# PCBPayloadV6.net
KiCad netlist of a schematic drawn in EAGLE
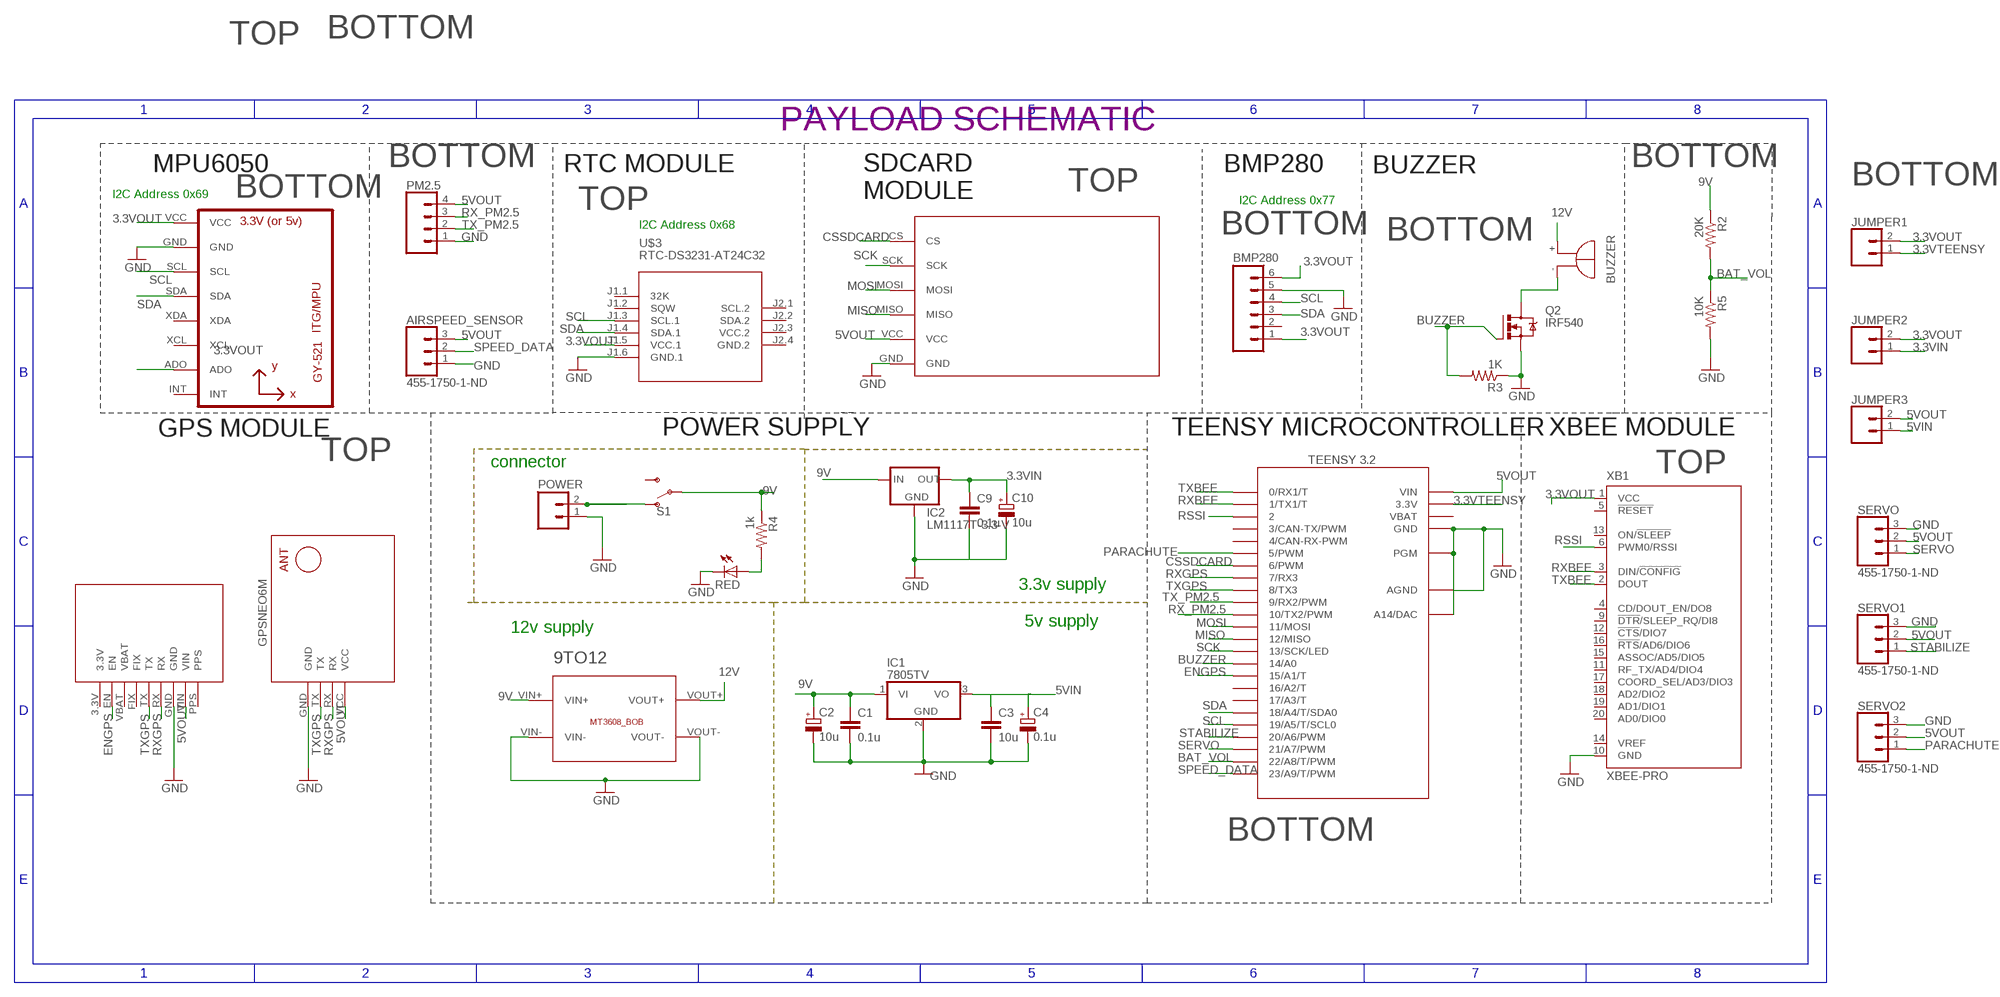
[diagram p0: schematic, sheet 1]

(export (version "E")
  (design (tool "Eeschema 10.0.6"))
  (components
    (comp (ref "9TO12")
      (value "BREAKOUTS_MT3608_BOB")
      (footprint "eagle-import:BREAKOUTS_MT3608_BOB")
      (libsource (lib "eagle-import") (part "BREAKOUTS_MT3608_BOB"))
    )
    (comp (ref "AIRSPEED_SENSOR")
      (value "455-1750-1-ND")
      (footprint "eagle-import:1X03")
      (libsource (lib "eagle-import") (part "CONN_03"))
    )
    (comp (ref "BMP280")
      (value "M06")
      (footprint "eagle-import:06P")
      (libsource (lib "eagle-import") (part "M06"))
    )
    (comp (ref "C1")
      (value "0.1u")
      (footprint "eagle-import:C025-025X050")
      (libsource (lib "eagle-import") (part "C-EU025-025X050"))
    )
    (comp (ref "C2")
      (value "10u")
      (footprint "eagle-import:E2,5-6")
      (libsource (lib "eagle-import") (part "CPOL-EUE2.5-6"))
    )
    (comp (ref "C3")
      (value "10u")
      (footprint "eagle-import:C025-025X050")
      (libsource (lib "eagle-import") (part "C-EU025-025X050"))
    )
    (comp (ref "C4")
      (value "0.1u")
      (footprint "eagle-import:E2,5-6")
      (libsource (lib "eagle-import") (part "CPOL-EUE2.5-6"))
    )
    (comp (ref "C9")
      (value "0.1u")
      (footprint "eagle-import:C025-025X050")
      (libsource (lib "eagle-import") (part "C-EU025-025X050"))
    )
    (comp (ref "C10")
      (value "10u")
      (footprint "eagle-import:E2,5-6")
      (libsource (lib "eagle-import") (part "CPOL-EUE2.5-6"))
    )
    (comp (ref "IC1")
      (value "7805TV")
      (footprint "eagle-import:TO220V")
      (libsource (lib "eagle-import") (part "78TV05"))
    )
    (comp (ref "IC2")
      (value "LM1117T-3.3-V")
      (footprint "eagle-import:TO220V")
      (libsource (lib "eagle-import") (part "LM1117T--V3.3"))
    )
    (comp (ref "JUMPER1")
      (value "CONN_02")
      (footprint "eagle-import:1X02")
      (libsource (lib "eagle-import") (part "CONN_02"))
    )
    (comp (ref "JUMPER2")
      (value "CONN_02")
      (footprint "eagle-import:1X02")
      (libsource (lib "eagle-import") (part "CONN_02"))
    )
    (comp (ref "JUMPER3")
      (value "CONN_02")
      (footprint "eagle-import:1X02")
      (libsource (lib "eagle-import") (part "CONN_02"))
    )
    (comp (ref "PM2.5")
      (value "CONN_04")
      (footprint "eagle-import:1X04")
      (libsource (lib "eagle-import") (part "CONN_04"))
    )
    (comp (ref "POWER")
      (value "CEDT_JANUARY_2015_V5_M02")
      (footprint "eagle-import:CEDT_JANUARY_2015_V5_02P")
      (libsource (lib "eagle-import") (part "CEDT_JANUARY_2015_V5_M02"))
    )
    (comp (ref "Q2")
      (value "IRF540")
      (footprint "eagle-import:TO220BV")
      (libsource (lib "eagle-import") (part "IRF540"))
    )
    (comp (ref "R2")
      (value "20K")
      (footprint "eagle-import:0204_7")
      (libsource (lib "eagle-import") (part "R-US_0204/7"))
    )
    (comp (ref "R3")
      (value "1K")
      (footprint "eagle-import:0204_7")
      (libsource (lib "eagle-import") (part "R-US_0204/7"))
    )
    (comp (ref "R4")
      (value "1k")
      (footprint "eagle-import:0204_7")
      (libsource (lib "eagle-import") (part "R-US_0204/7"))
    )
    (comp (ref "R5")
      (value "10K")
      (footprint "eagle-import:0204_7")
      (libsource (lib "eagle-import") (part "R-US_0204/7"))
    )
    (comp (ref "RED")
      (value "red")
      (footprint "eagle-import:LED3MM")
      (libsource (lib "eagle-import") (part "LED3MM"))
    )
    (comp (ref "S1")
      (value "SWITCH-SPDT-PTH-11.6X4.0MM")
      (footprint "eagle-import:SWITCH_SPDT_PTH_11.6X4.0MM")
      (libsource (lib "eagle-import") (part "SWITCH-SPDT-PTH-11.6X4.0MM"))
    )
    (comp (ref "SERVO")
      (value "455-1750-1-ND")
      (footprint "eagle-import:1X03")
      (libsource (lib "eagle-import") (part "CONN_03"))
    )
    (comp (ref "SERVO1")
      (value "455-1750-1-ND")
      (footprint "eagle-import:1X03")
      (libsource (lib "eagle-import") (part "CONN_03"))
    )
    (comp (ref "SERVO2")
      (value "455-1750-1-ND")
      (footprint "eagle-import:1X03")
      (libsource (lib "eagle-import") (part "CONN_03"))
    )
    (comp (ref "SG1")
      (value "BUZZER_EB2209A")
      (footprint "eagle-import:BUZZER_EB2209A")
      (libsource (lib "eagle-import") (part "BUZZER_EB2209A"))
    )
    (comp (ref "U$1")
      (value "GPS-RECEIVER-NEO6M")
      (footprint "eagle-import:GPS-RECEIVER-NEO6M")
      (libsource (lib "eagle-import") (part "GPS-RECEIVER-NEO6M"))
    )
    (comp (ref "U$2")
      (value "TEENSY_3.1-3.2_OUTER_ROW")
      (footprint "eagle-import:TEENSY_3.0-3.2&LC_OUTER_ROW")
      (libsource (lib "eagle-import") (part "TEENSY_3.1-3.2_OUTER_ROW"))
    )
    (comp (ref "U$3")
      (value "RTC-DS3231-AT24C32")
      (footprint "eagle-import:RTC-DS3231-AT24C32")
      (libsource (lib "eagle-import") (part "RTC-DS3231-AT24C32"))
    )
    (comp (ref "U$4")
      (value "ADAFRUIT_GPS")
      (footprint "eagle-import:ADAFRUIT_GPS")
      (libsource (lib "eagle-import") (part "ADAFRUIT_GPS"))
    )
    (comp (ref "U$5")
      (value "SDCARD")
      (footprint "eagle-import:M0SDCARDMODULE")
      (libsource (lib "eagle-import") (part "SDCARD"))
    )
    (comp (ref "U1")
      (value "GY-521MPU6050")
      (footprint "eagle-import:GY-521")
      (libsource (lib "eagle-import") (part "GY-521MPU6050"))
    )
    (comp (ref "XB1")
      (value "XBEE-PRO")
      (footprint "eagle-import:XBEE-PRO")
      (fields (field (name "MPN") "XBP24-AWI-001"))
      (libsource (lib "eagle-import") (part "XBEE-PRO"))
    )
  )
  (nets
    (net (code "1") (name "/3.3VIN") (class "Default")
      (node (ref "C10") (pin "+") (pinfunction "+_+") (pintype "passive"))
      (node (ref "C9") (pin "1") (pinfunction "1_1") (pintype "passive"))
      (node (ref "IC2") (pin "2") (pinfunction "OUT_2") (pintype "passive"))
      (node (ref "JUMPER2") (pin "1") (pinfunction "1_1") (pintype "passive"))
    )
    (net (code "2") (name "/3.3VOUT") (class "Default")
      (node (ref "BMP280") (pin "1") (pinfunction "1_1") (pintype "passive"))
      (node (ref "BMP280") (pin "6") (pinfunction "6_6") (pintype "passive"))
      (node (ref "JUMPER1") (pin "2") (pinfunction "2_2") (pintype "passive"))
      (node (ref "JUMPER2") (pin "2") (pinfunction "2_2") (pintype "passive"))
      (node (ref "U$3") (pin "J1.5") (pinfunction "VCC.1_J1.5") (pintype "power_in"))
      (node (ref "U1") (pin "ADO") (pinfunction "ADO_ADO") (pintype "bidirectional"))
      (node (ref "U1") (pin "VCC") (pinfunction "VCC_VCC") (pintype "bidirectional"))
      (node (ref "XB1") (pin "1") (pinfunction "VCC_1") (pintype "power_in"))
    )
    (net (code "3") (name "/3.3VTEENSY") (class "Default")
      (node (ref "JUMPER1") (pin "1") (pinfunction "1_1") (pintype "passive"))
      (node (ref "U$2") (pin "3.3V") (pinfunction "3.3V_3.3V") (pintype "power_in"))
      (node (ref "U$2") (pin "3.3V1") (pinfunction "3.3V_3.3V1") (pintype "power_in"))
    )
    (net (code "4") (name "/5VIN") (class "Default")
      (node (ref "C3") (pin "1") (pinfunction "1_1") (pintype "passive"))
      (node (ref "C4") (pin "+") (pinfunction "+_+") (pintype "passive"))
      (node (ref "IC1") (pin "3") (pinfunction "VO_3") (pintype "passive"))
      (node (ref "JUMPER3") (pin "1") (pinfunction "1_1") (pintype "passive"))
    )
    (net (code "5") (name "/5VOUT") (class "Default")
      (node (ref "AIRSPEED_SENSOR") (pin "3") (pinfunction "3_3") (pintype "passive"))
      (node (ref "JUMPER3") (pin "2") (pinfunction "2_2") (pintype "passive"))
      (node (ref "PM2.5") (pin "4") (pinfunction "4_4") (pintype "passive"))
      (node (ref "SERVO") (pin "2") (pinfunction "2_2") (pintype "passive"))
      (node (ref "SERVO1") (pin "2") (pinfunction "2_2") (pintype "passive"))
      (node (ref "SERVO2") (pin "2") (pinfunction "2_2") (pintype "passive"))
      (node (ref "U$1") (pin "VCC") (pinfunction "VCC_VCC") (pintype "power_in"))
      (node (ref "U$2") (pin "VIN") (pinfunction "VIN_VIN") (pintype "power_in"))
      (node (ref "U$4") (pin "VIN") (pinfunction "VIN_VIN") (pintype "bidirectional"))
      (node (ref "U$5") (pin "VCC") (pinfunction "VCC_VCC") (pintype "bidirectional"))
    )
    (net (code "6") (name "/9V") (class "Default")
      (node (ref "9TO12") (pin "VIN+") (pinfunction "VIN+_VIN+") (pintype "bidirectional"))
      (node (ref "C1") (pin "1") (pinfunction "1_1") (pintype "passive"))
      (node (ref "C2") (pin "+") (pinfunction "+_+") (pintype "passive"))
      (node (ref "IC1") (pin "1") (pinfunction "VI_1") (pintype "input"))
      (node (ref "IC2") (pin "3") (pinfunction "IN_3") (pintype "input"))
      (node (ref "R2") (pin "1") (pinfunction "1_1") (pintype "passive"))
      (node (ref "R4") (pin "1") (pinfunction "1_1") (pintype "passive"))
      (node (ref "S1") (pin "2") (pinfunction "P_2") (pintype "passive"))
    )
    (net (code "7") (name "/12V") (class "Default")
      (node (ref "9TO12") (pin "VOUT+") (pinfunction "VOUT+_VOUT+") (pintype "bidirectional"))
      (node (ref "SG1") (pin "+") (pinfunction "+_+") (pintype "passive"))
    )
    (net (code "8") (name "/BAT_VOL") (class "Default")
      (node (ref "R2") (pin "2") (pinfunction "2_2") (pintype "passive"))
      (node (ref "R5") (pin "1") (pinfunction "1_1") (pintype "passive"))
      (node (ref "U$2") (pin "22/A8") (pinfunction "22/A8/T/PWM_22/A8") (pintype "bidirectional"))
    )
    (net (code "9") (name "/BUZZER") (class "Default")
      (node (ref "Q2") (pin "G") (pinfunction "G_G") (pintype "passive"))
      (node (ref "R3") (pin "2") (pinfunction "2_2") (pintype "passive"))
      (node (ref "U$2") (pin "14/A0") (pinfunction "14/A0_14/A0") (pintype "bidirectional"))
    )
    (net (code "10") (name "/CSSDCARD") (class "Default")
      (node (ref "U$2") (pin "6") (pinfunction "6/PWM_6") (pintype "bidirectional"))
      (node (ref "U$5") (pin "CS") (pinfunction "CS_CS") (pintype "bidirectional"))
    )
    (net (code "11") (name "/ENGPS") (class "Default")
      (node (ref "U$2") (pin "15/A1") (pinfunction "15/A1/T_15/A1") (pintype "bidirectional"))
      (node (ref "U$4") (pin "EN") (pinfunction "EN_EN") (pintype "bidirectional"))
    )
    (net (code "12") (name "/GND.2") (class "Default")
      (node (ref "U$3") (pin "J2.4") (pinfunction "GND.2_J2.4") (pintype "power_in"))
    )
    (net (code "13") (name "/MISO") (class "Default")
      (node (ref "U$2") (pin "12") (pinfunction "12/MISO_12") (pintype "bidirectional"))
      (node (ref "U$5") (pin "MISO") (pinfunction "MISO_MISO") (pintype "bidirectional"))
    )
    (net (code "14") (name "/MOSI") (class "Default")
      (node (ref "U$2") (pin "11") (pinfunction "11/MOSI_11") (pintype "bidirectional"))
      (node (ref "U$5") (pin "MOSI") (pinfunction "MOSI_MOSI") (pintype "bidirectional"))
    )
    (net (code "15") (name "/PARACHUTE") (class "Default")
      (node (ref "SERVO2") (pin "1") (pinfunction "1_1") (pintype "passive"))
      (node (ref "U$2") (pin "5") (pinfunction "5/PWM_5") (pintype "bidirectional"))
    )
    (net (code "16") (name "/RSSI") (class "Default")
      (node (ref "U$2") (pin "2") (pinfunction "2_2") (pintype "bidirectional"))
      (node (ref "XB1") (pin "6") (pinfunction "PWM0/RSSI_6") (pintype "output"))
    )
    (net (code "17") (name "/RXBEE") (class "Default")
      (node (ref "U$2") (pin "1") (pinfunction "1/TX1/T_1") (pintype "bidirectional"))
      (node (ref "XB1") (pin "3") (pinfunction "DIN/~{CONFIG}_3") (pintype "input"))
    )
    (net (code "18") (name "/RXGPS") (class "Default")
      (node (ref "U$1") (pin "RX") (pinfunction "RX_RX") (pintype "bidirectional"))
      (node (ref "U$2") (pin "7") (pinfunction "7/RX3_7") (pintype "bidirectional"))
      (node (ref "U$4") (pin "RX") (pinfunction "RX_RX") (pintype "bidirectional"))
    )
    (net (code "19") (name "/RX_PM2.5") (class "Default")
      (node (ref "PM2.5") (pin "3") (pinfunction "3_3") (pintype "passive"))
      (node (ref "U$2") (pin "10") (pinfunction "10/TX2/PWM_10") (pintype "bidirectional"))
    )
    (net (code "20") (name "/SCK") (class "Default")
      (node (ref "U$2") (pin "13") (pinfunction "13/SCK/LED_13") (pintype "bidirectional"))
      (node (ref "U$5") (pin "SCK") (pinfunction "SCK_SCK") (pintype "bidirectional"))
    )
    (net (code "21") (name "/SCL") (class "Default")
      (node (ref "BMP280") (pin "4") (pinfunction "4_4") (pintype "passive"))
      (node (ref "U$2") (pin "19/A5") (pinfunction "19/A5/T/SCL0_19/A5") (pintype "bidirectional"))
      (node (ref "U$3") (pin "J1.3") (pinfunction "SCL.1_J1.3") (pintype "bidirectional"))
      (node (ref "U1") (pin "SCL") (pinfunction "SCL_SCL") (pintype "bidirectional"))
    )
    (net (code "22") (name "/SDA") (class "Default")
      (node (ref "BMP280") (pin "3") (pinfunction "3_3") (pintype "passive"))
      (node (ref "U$2") (pin "18/A4") (pinfunction "18/A4/T/SDA0_18/A4") (pintype "bidirectional"))
      (node (ref "U$3") (pin "J1.4") (pinfunction "SDA.1_J1.4") (pintype "bidirectional"))
      (node (ref "U1") (pin "SDA") (pinfunction "SDA_SDA") (pintype "bidirectional"))
    )
    (net (code "23") (name "/SERVO") (class "Default")
      (node (ref "SERVO") (pin "1") (pinfunction "1_1") (pintype "passive"))
      (node (ref "U$2") (pin "21/A7") (pinfunction "21/A7/PWM_21/A7") (pintype "bidirectional"))
    )
    (net (code "24") (name "/SPEED_DATA") (class "Default")
      (node (ref "AIRSPEED_SENSOR") (pin "2") (pinfunction "2_2") (pintype "passive"))
      (node (ref "U$2") (pin "23/A9") (pinfunction "23/A9/T/PWM_23/A9") (pintype "bidirectional"))
    )
    (net (code "25") (name "/STABILIZE") (class "Default")
      (node (ref "SERVO1") (pin "1") (pinfunction "1_1") (pintype "passive"))
      (node (ref "U$2") (pin "20/A6") (pinfunction "20/A6/PWM_20/A6") (pintype "bidirectional"))
    )
    (net (code "26") (name "/TXBEE") (class "Default")
      (node (ref "U$2") (pin "0") (pinfunction "0/RX1/T_0") (pintype "bidirectional"))
      (node (ref "XB1") (pin "2") (pinfunction "DOUT_2") (pintype "output"))
    )
    (net (code "27") (name "/TXGPS") (class "Default")
      (node (ref "U$1") (pin "TX") (pinfunction "TX_TX") (pintype "bidirectional"))
      (node (ref "U$2") (pin "8") (pinfunction "8/TX3_8") (pintype "bidirectional"))
      (node (ref "U$4") (pin "TX") (pinfunction "TX_TX") (pintype "bidirectional"))
    )
    (net (code "28") (name "/TX_PM2.5") (class "Default")
      (node (ref "PM2.5") (pin "2") (pinfunction "2_2") (pintype "passive"))
      (node (ref "U$2") (pin "9") (pinfunction "9/RX2/PWM_9") (pintype "bidirectional"))
    )
    (net (code "29") (name "/VBAT") (class "Default")
      (node (ref "U$2") (pin "VBAT") (pinfunction "VBAT_VBAT") (pintype "power_in"))
    )
    (net (code "30") (name "/VCC.2") (class "Default")
      (node (ref "U$3") (pin "J2.3") (pinfunction "VCC.2_J2.3") (pintype "power_in"))
    )
    (net (code "31") (name "GND") (class "Default")
      (node (ref "9TO12") (pin "VIN-") (pinfunction "VIN-_VIN-") (pintype "bidirectional"))
      (node (ref "9TO12") (pin "VOUT-") (pinfunction "VOUT-_VOUT-") (pintype "bidirectional"))
      (node (ref "AIRSPEED_SENSOR") (pin "1") (pinfunction "1_1") (pintype "passive"))
      (node (ref "BMP280") (pin "5") (pinfunction "5_5") (pintype "passive"))
      (node (ref "C1") (pin "2") (pinfunction "2_2") (pintype "passive"))
      (node (ref "C10") (pin "-") (pinfunction "-_-") (pintype "passive"))
      (node (ref "C2") (pin "-") (pinfunction "-_-") (pintype "passive"))
      (node (ref "C3") (pin "2") (pinfunction "2_2") (pintype "passive"))
      (node (ref "C4") (pin "-") (pinfunction "-_-") (pintype "passive"))
      (node (ref "C9") (pin "2") (pinfunction "2_2") (pintype "passive"))
      (node (ref "IC1") (pin "2") (pinfunction "GND_2") (pintype "passive"))
      (node (ref "IC2") (pin "1") (pinfunction "GND_1") (pintype "input"))
      (node (ref "PM2.5") (pin "1") (pinfunction "1_1") (pintype "passive"))
      (node (ref "POWER") (pin "1") (pinfunction "1_1") (pintype "passive"))
      (node (ref "Q2") (pin "S") (pinfunction "S_S") (pintype "passive"))
      (node (ref "R3") (pin "1") (pinfunction "1_1") (pintype "passive"))
      (node (ref "R5") (pin "2") (pinfunction "2_2") (pintype "passive"))
      (node (ref "RED") (pin "K") (pinfunction "C_K") (pintype "passive"))
      (node (ref "SERVO") (pin "3") (pinfunction "3_3") (pintype "passive"))
      (node (ref "SERVO1") (pin "3") (pinfunction "3_3") (pintype "passive"))
      (node (ref "SERVO2") (pin "3") (pinfunction "3_3") (pintype "passive"))
      (node (ref "U$1") (pin "GND") (pinfunction "GND_GND") (pintype "bidirectional"))
      (node (ref "U$2") (pin "AGND") (pinfunction "AGND_AGND") (pintype "power_in"))
      (node (ref "U$2") (pin "GND") (pinfunction "GND_GND") (pintype "power_in"))
      (node (ref "U$2") (pin "GND1") (pinfunction "GND_GND1") (pintype "power_in"))
      (node (ref "U$2") (pin "PGM") (pinfunction "PGM_PGM") (pintype "bidirectional"))
      (node (ref "U$2") (pin "RESET/DAC") (pinfunction "A14/DAC_RESET/DAC") (pintype "bidirectional"))
      (node (ref "U$3") (pin "J1.6") (pinfunction "GND.1_J1.6") (pintype "power_in"))
      (node (ref "U$4") (pin "GND") (pinfunction "GND_GND") (pintype "bidirectional"))
      (node (ref "U$5") (pin "GND") (pinfunction "GND_GND") (pintype "bidirectional"))
      (node (ref "U1") (pin "GND") (pinfunction "GND_GND") (pintype "bidirectional"))
      (node (ref "XB1") (pin "10") (pinfunction "GND_10") (pintype "power_in"))
    )
    (net (code "32") (name "Net-(Q2-PadD)") (class "Default")
      (node (ref "Q2") (pin "D") (pinfunction "D_D") (pintype "passive"))
      (node (ref "SG1") (pin "-") (pinfunction "-_-") (pintype "passive"))
    )
    (net (code "33") (name "Net-(R4-Pad2)") (class "Default")
      (node (ref "R4") (pin "2") (pinfunction "2_2") (pintype "passive"))
      (node (ref "RED") (pin "A") (pinfunction "A_A") (pintype "passive"))
    )
    (net (code "34") (name "Net-(S1-O)") (class "Default")
      (node (ref "POWER") (pin "2") (pinfunction "2_2") (pintype "passive"))
      (node (ref "S1") (pin "1") (pinfunction "O_1") (pintype "passive"))
    )
    (net (code "35") (name "unconnected-(BMP280-Pad2)") (class "Default")
      (node (ref "BMP280") (pin "2") (pinfunction "2_2") (pintype "passive"))
    )
    (net (code "36") (name "unconnected-(S1-S-Pad3)") (class "Default")
      (node (ref "S1") (pin "3") (pinfunction "S_3") (pintype "passive"))
    )
    (net (code "37") (name "unconnected-(U$2-3{slash}CAN-TX{slash}PWM-Pad3)") (class "Default")
      (node (ref "U$2") (pin "3") (pinfunction "3/CAN-TX/PWM_3") (pintype "bidirectional"))
    )
    (net (code "38") (name "unconnected-(U$2-4{slash}CAN-RX-PWM-Pad4)") (class "Default")
      (node (ref "U$2") (pin "4") (pinfunction "4/CAN-RX-PWM_4") (pintype "bidirectional"))
    )
    (net (code "39") (name "unconnected-(U$2-16{slash}A2{slash}T-Pad16{slash}A2)") (class "Default")
      (node (ref "U$2") (pin "16/A2") (pinfunction "16/A2/T_16/A2") (pintype "bidirectional"))
    )
    (net (code "40") (name "unconnected-(U$2-17{slash}A3{slash}T-Pad17{slash}A3)") (class "Default")
      (node (ref "U$2") (pin "17/A3") (pinfunction "17/A3/T_17/A3") (pintype "bidirectional"))
    )
    (net (code "41") (name "unconnected-(U$3-32K-PadJ1.1)") (class "Default")
      (node (ref "U$3") (pin "J1.1") (pinfunction "32K_J1.1") (pintype "bidirectional"))
    )
    (net (code "42") (name "unconnected-(U$3-SCL.2-PadJ2.1)") (class "Default")
      (node (ref "U$3") (pin "J2.1") (pinfunction "SCL.2_J2.1") (pintype "bidirectional"))
    )
    (net (code "43") (name "unconnected-(U$3-SDA.2-PadJ2.2)") (class "Default")
      (node (ref "U$3") (pin "J2.2") (pinfunction "SDA.2_J2.2") (pintype "bidirectional"))
    )
    (net (code "44") (name "unconnected-(U$3-SQW-PadJ1.2)") (class "Default")
      (node (ref "U$3") (pin "J1.2") (pinfunction "SQW_J1.2") (pintype "bidirectional"))
    )
    (net (code "45") (name "unconnected-(U$4-Pad3.3V)") (class "Default")
      (node (ref "U$4") (pin "3.3V") (pinfunction "3.3V_3.3V") (pintype "bidirectional"))
    )
    (net (code "46") (name "unconnected-(U$4-PadFIX)") (class "Default")
      (node (ref "U$4") (pin "FIX") (pinfunction "FIX_FIX") (pintype "bidirectional"))
    )
    (net (code "47") (name "unconnected-(U$4-PadPPS)") (class "Default")
      (node (ref "U$4") (pin "PPS") (pinfunction "PPS_PPS") (pintype "bidirectional"))
    )
    (net (code "48") (name "unconnected-(U$4-PadVBAT)") (class "Default")
      (node (ref "U$4") (pin "VBAT") (pinfunction "VBAT_VBAT") (pintype "bidirectional"))
    )
    (net (code "49") (name "unconnected-(U1-PadINT)") (class "Default")
      (node (ref "U1") (pin "INT") (pinfunction "INT_INT") (pintype "bidirectional"))
    )
    (net (code "50") (name "unconnected-(U1-PadXCL)") (class "Default")
      (node (ref "U1") (pin "XCL") (pinfunction "XCL_XCL") (pintype "bidirectional"))
    )
    (net (code "51") (name "unconnected-(U1-PadXDA)") (class "Default")
      (node (ref "U1") (pin "XDA") (pinfunction "XDA_XDA") (pintype "bidirectional"))
    )
    (net (code "52") (name "unconnected-(XB1-AD0{slash}DIO0-Pad20)") (class "Default")
      (node (ref "XB1") (pin "20") (pinfunction "AD0/DIO0_20") (pintype "bidirectional"))
    )
    (net (code "53") (name "unconnected-(XB1-AD1{slash}DIO1-Pad19)") (class "Default")
      (node (ref "XB1") (pin "19") (pinfunction "AD1/DIO1_19") (pintype "bidirectional"))
    )
    (net (code "54") (name "unconnected-(XB1-AD2{slash}DIO2-Pad18)") (class "Default")
      (node (ref "XB1") (pin "18") (pinfunction "AD2/DIO2_18") (pintype "bidirectional"))
    )
    (net (code "55") (name "unconnected-(XB1-ASSOC{slash}AD5{slash}DIO5-Pad15)") (class "Default")
      (node (ref "XB1") (pin "15") (pinfunction "ASSOC/AD5/DIO5_15") (pintype "bidirectional"))
    )
    (net (code "56") (name "unconnected-(XB1-CD{slash}DOUT_EN{slash}DO8-Pad4)") (class "Default")
      (node (ref "XB1") (pin "4") (pinfunction "CD/DOUT_EN/DO8_4") (pintype "output"))
    )
    (net (code "57") (name "unconnected-(XB1-COORD_SEL{slash}AD3{slash}DIO3-Pad17)") (class "Default")
      (node (ref "XB1") (pin "17") (pinfunction "COORD_SEL/AD3/DIO3_17") (pintype "bidirectional"))
    )
    (net (code "58") (name "unconnected-(XB1-ON{slash}~{SLEEP}-Pad13)") (class "Default")
      (node (ref "XB1") (pin "13") (pinfunction "ON/~{SLEEP}_13") (pintype "output"))
    )
    (net (code "59") (name "unconnected-(XB1-RF_TX{slash}AD4{slash}DIO4-Pad11)") (class "Default")
      (node (ref "XB1") (pin "11") (pinfunction "RF_TX/AD4/DIO4_11") (pintype "bidirectional"))
    )
    (net (code "60") (name "unconnected-(XB1-VREF-Pad14)") (class "Default")
      (node (ref "XB1") (pin "14") (pinfunction "VREF_14") (pintype "input"))
    )
    (net (code "61") (name "unconnected-(XB1-~{CTS}{slash}DIO7-Pad12)") (class "Default")
      (node (ref "XB1") (pin "12") (pinfunction "~{CTS}/DIO7_12") (pintype "bidirectional"))
    )
    (net (code "62") (name "unconnected-(XB1-~{DTR}{slash}SLEEP_RQ{slash}DI8-Pad9)") (class "Default")
      (node (ref "XB1") (pin "9") (pinfunction "~{DTR}/SLEEP_RQ/DI8_9") (pintype "bidirectional"))
    )
    (net (code "63") (name "unconnected-(XB1-~{RESET}-Pad5)") (class "Default")
      (node (ref "XB1") (pin "5") (pinfunction "~{RESET}_5") (pintype "input"))
    )
    (net (code "64") (name "unconnected-(XB1-~{RTS}{slash}AD6{slash}DIO6-Pad16)") (class "Default")
      (node (ref "XB1") (pin "16") (pinfunction "~{RTS}/AD6/DIO6_16") (pintype "bidirectional"))
    )
  )
)
